# module_tester-v01.net
KiCad netlist of a schematic drawn in EAGLE
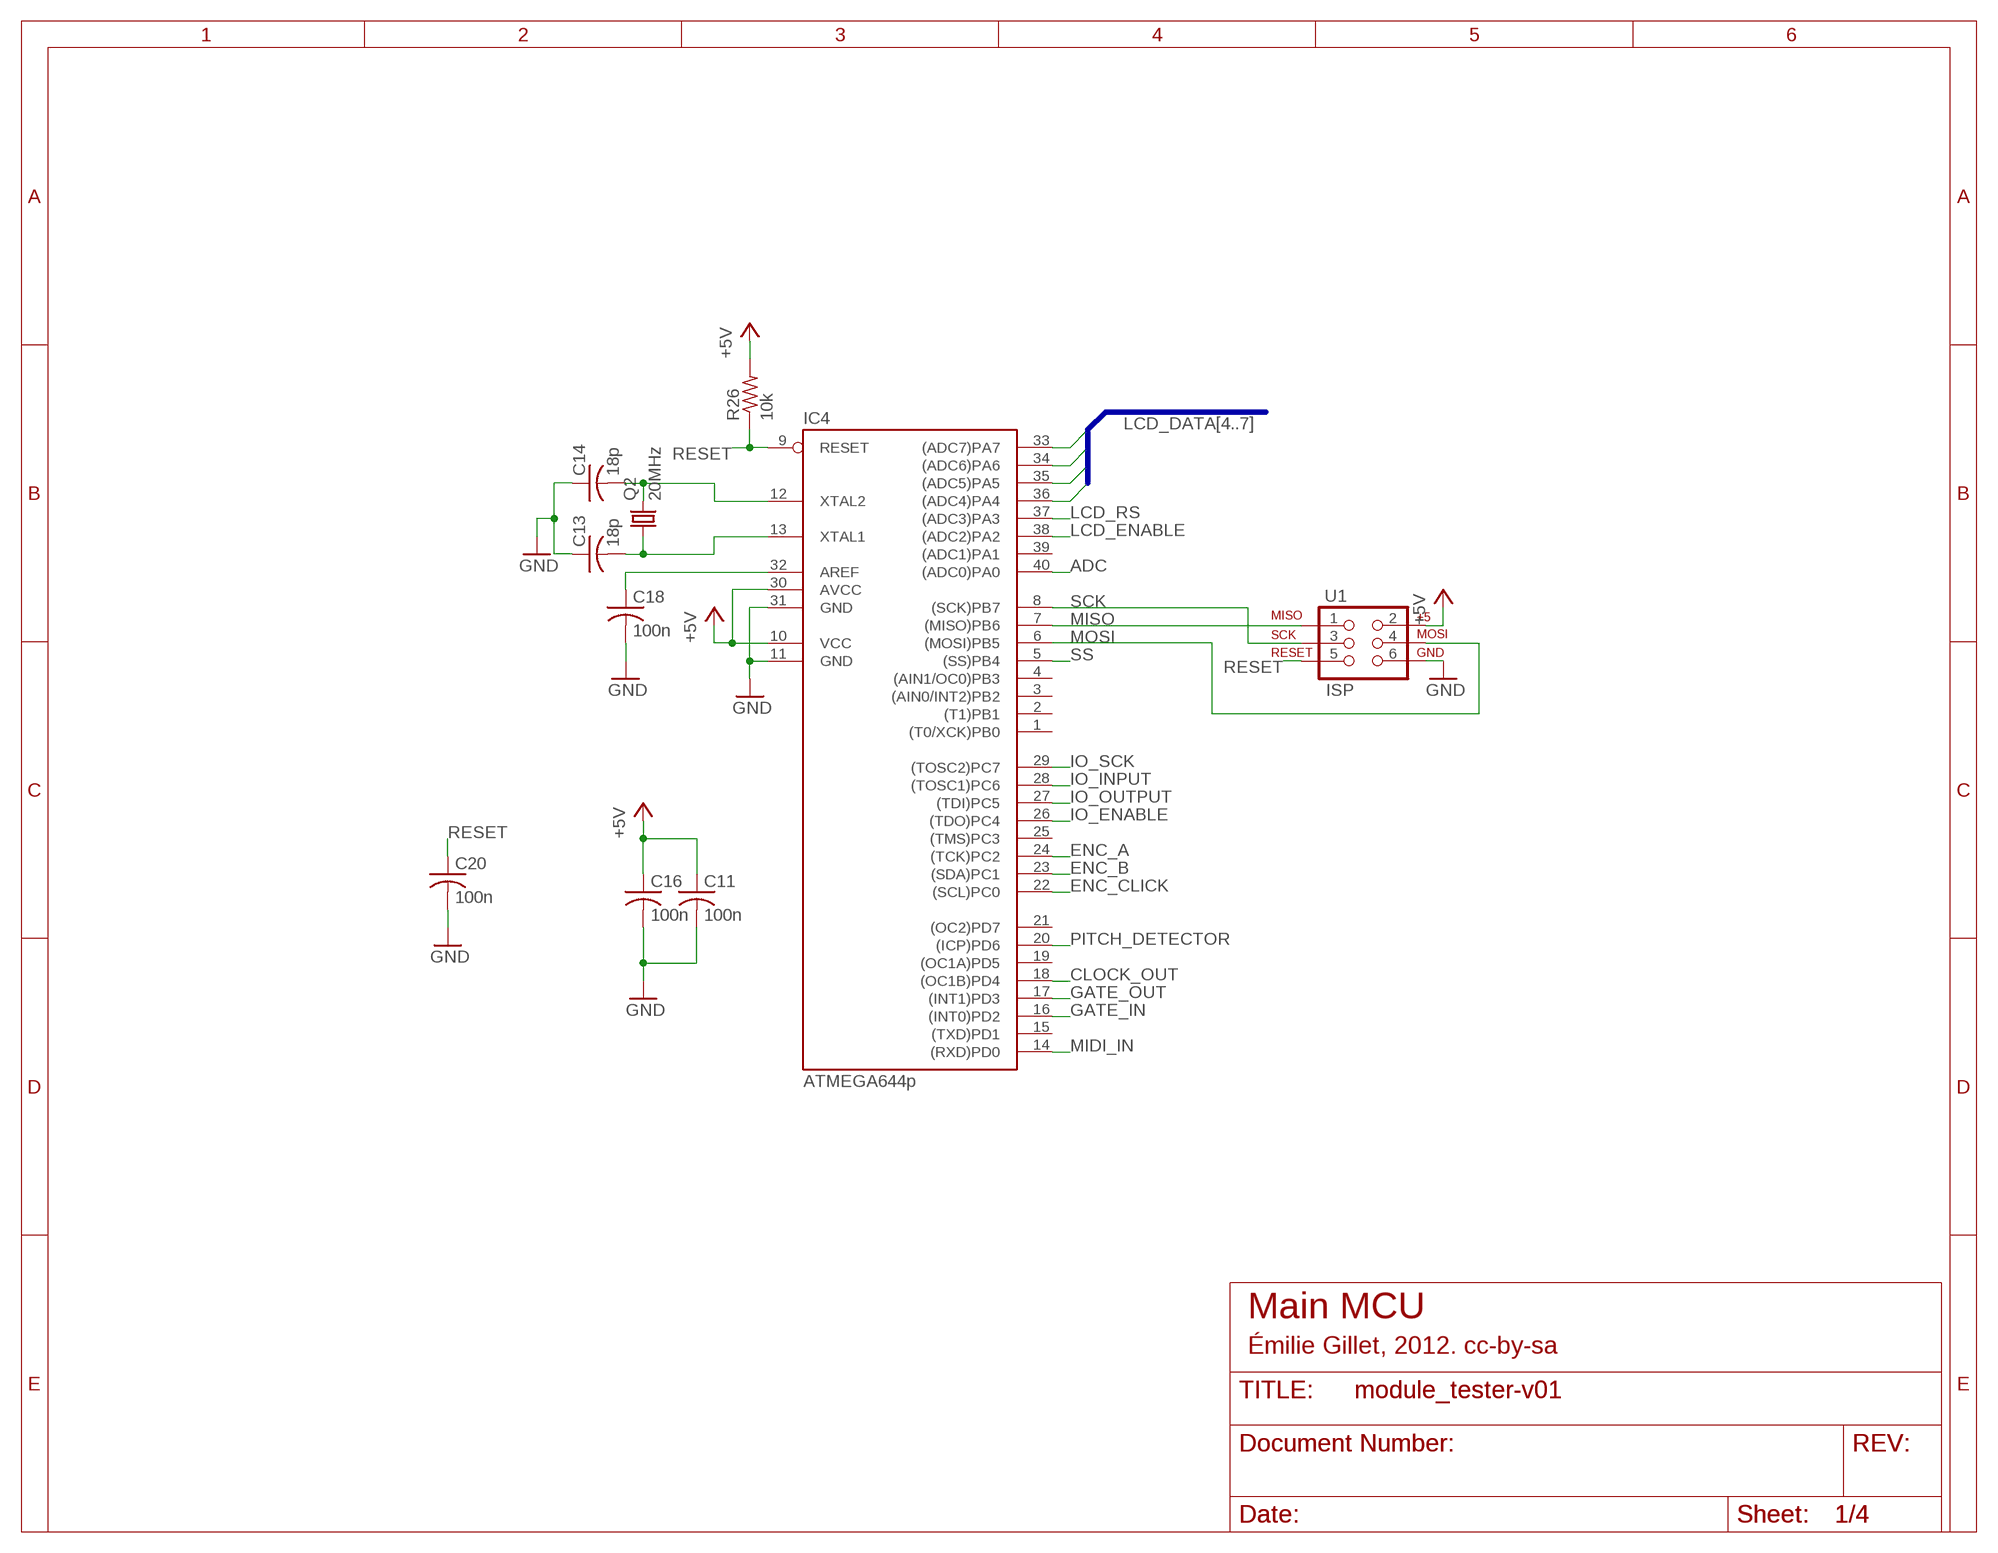
[diagram p0: schematic, sheet 1]
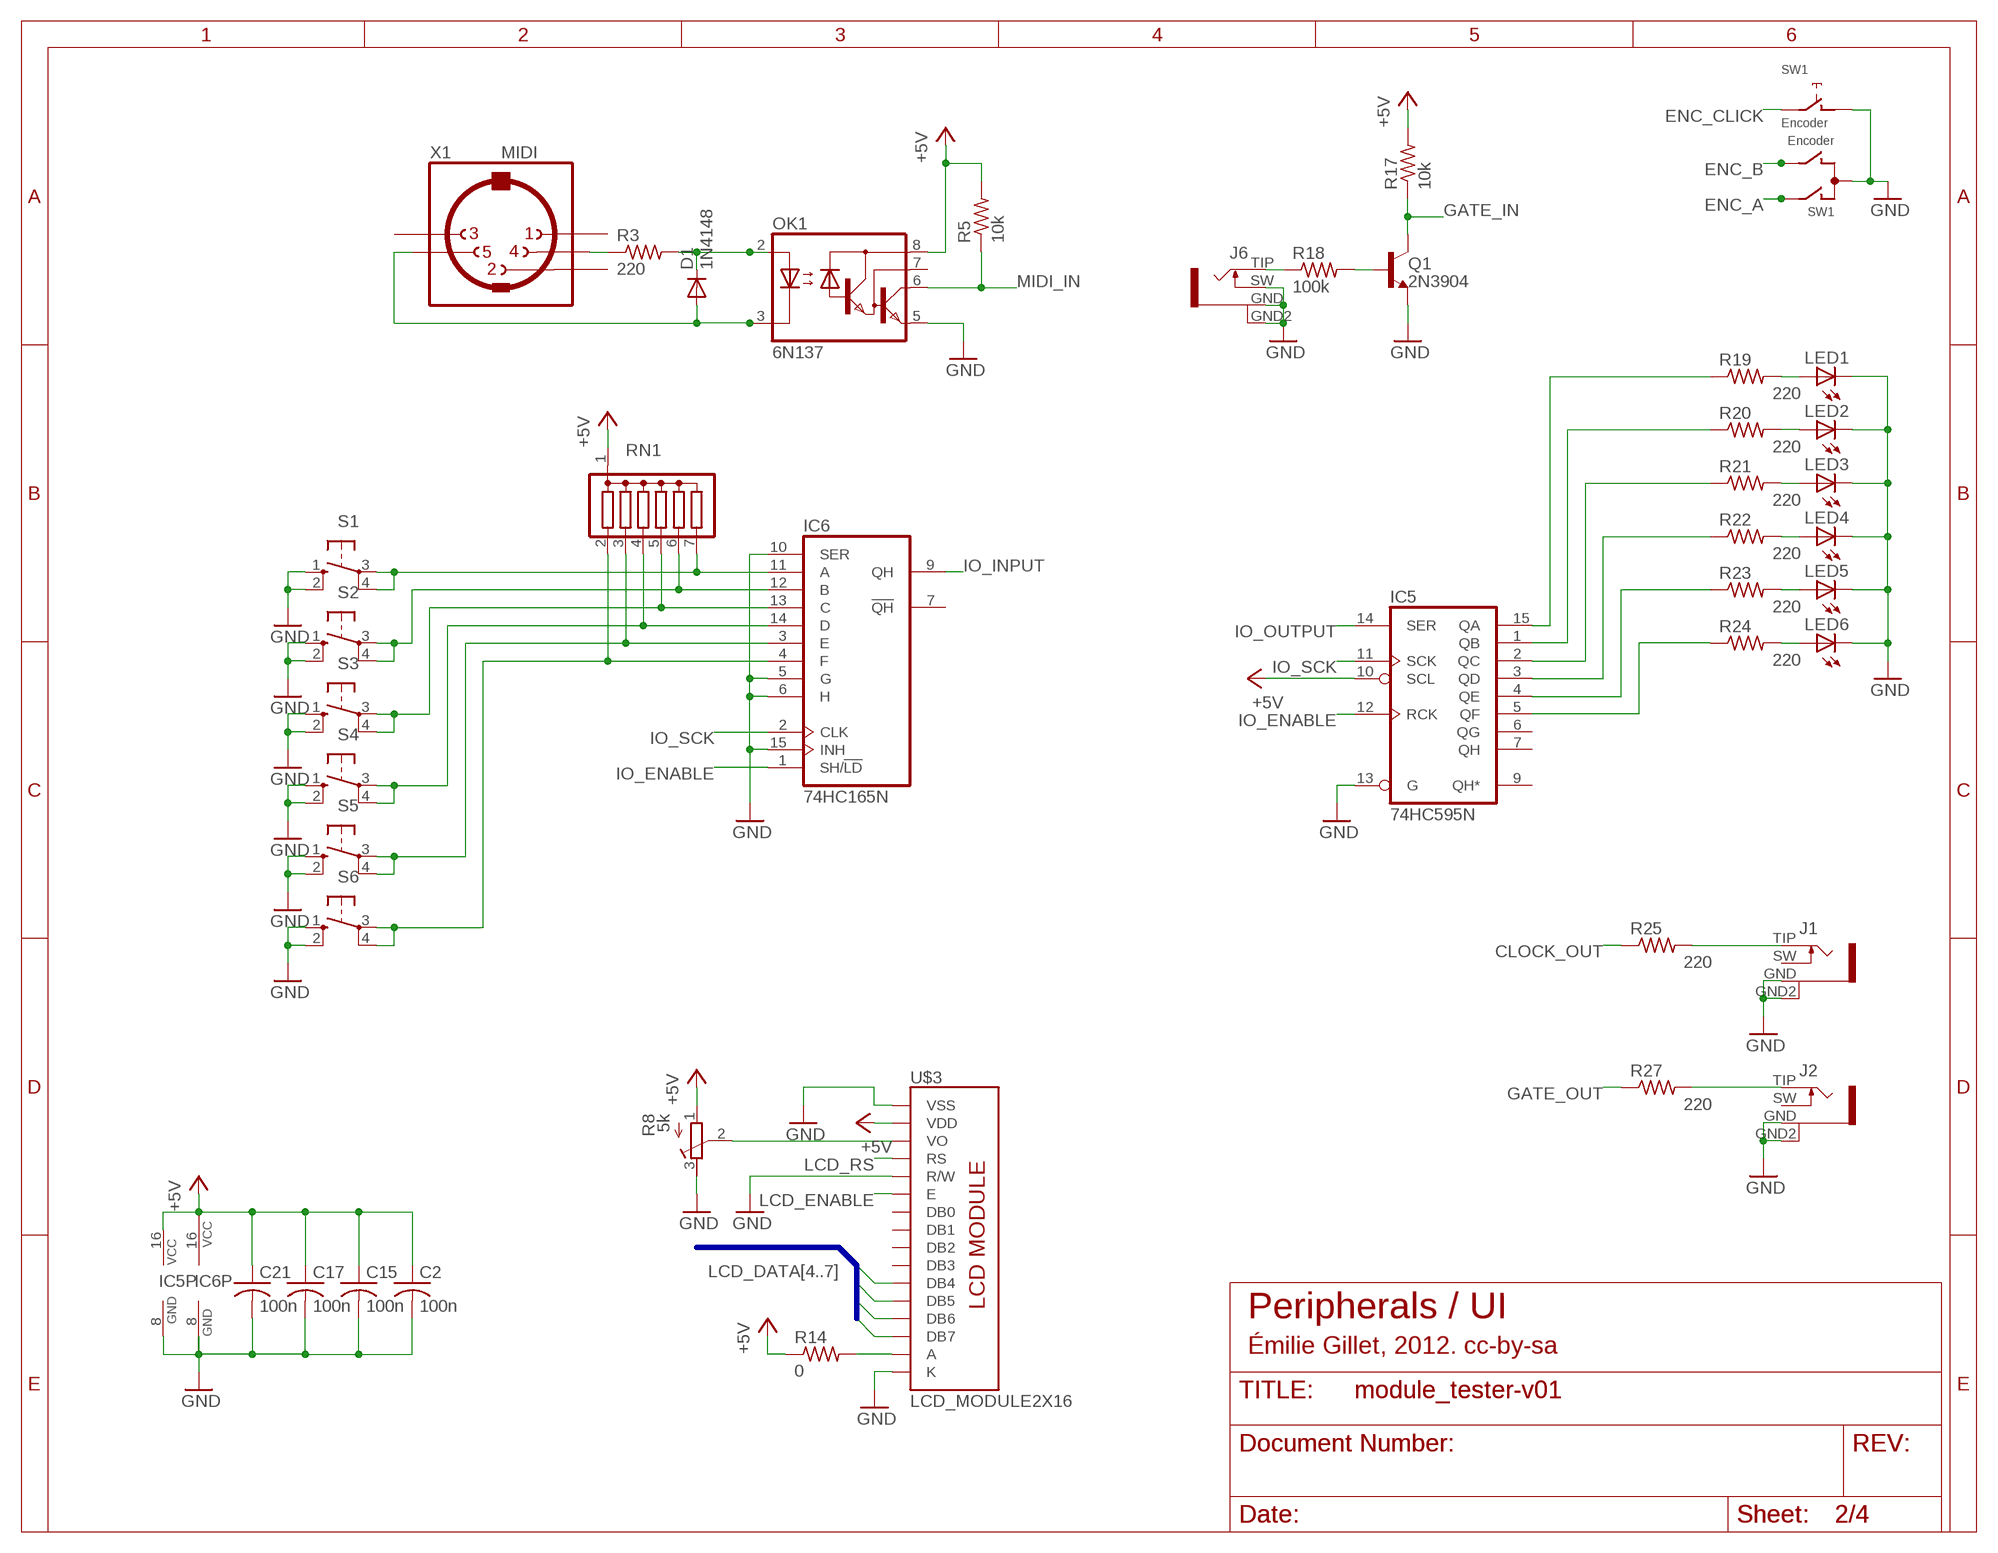
[diagram p1: schematic, sheet 2]
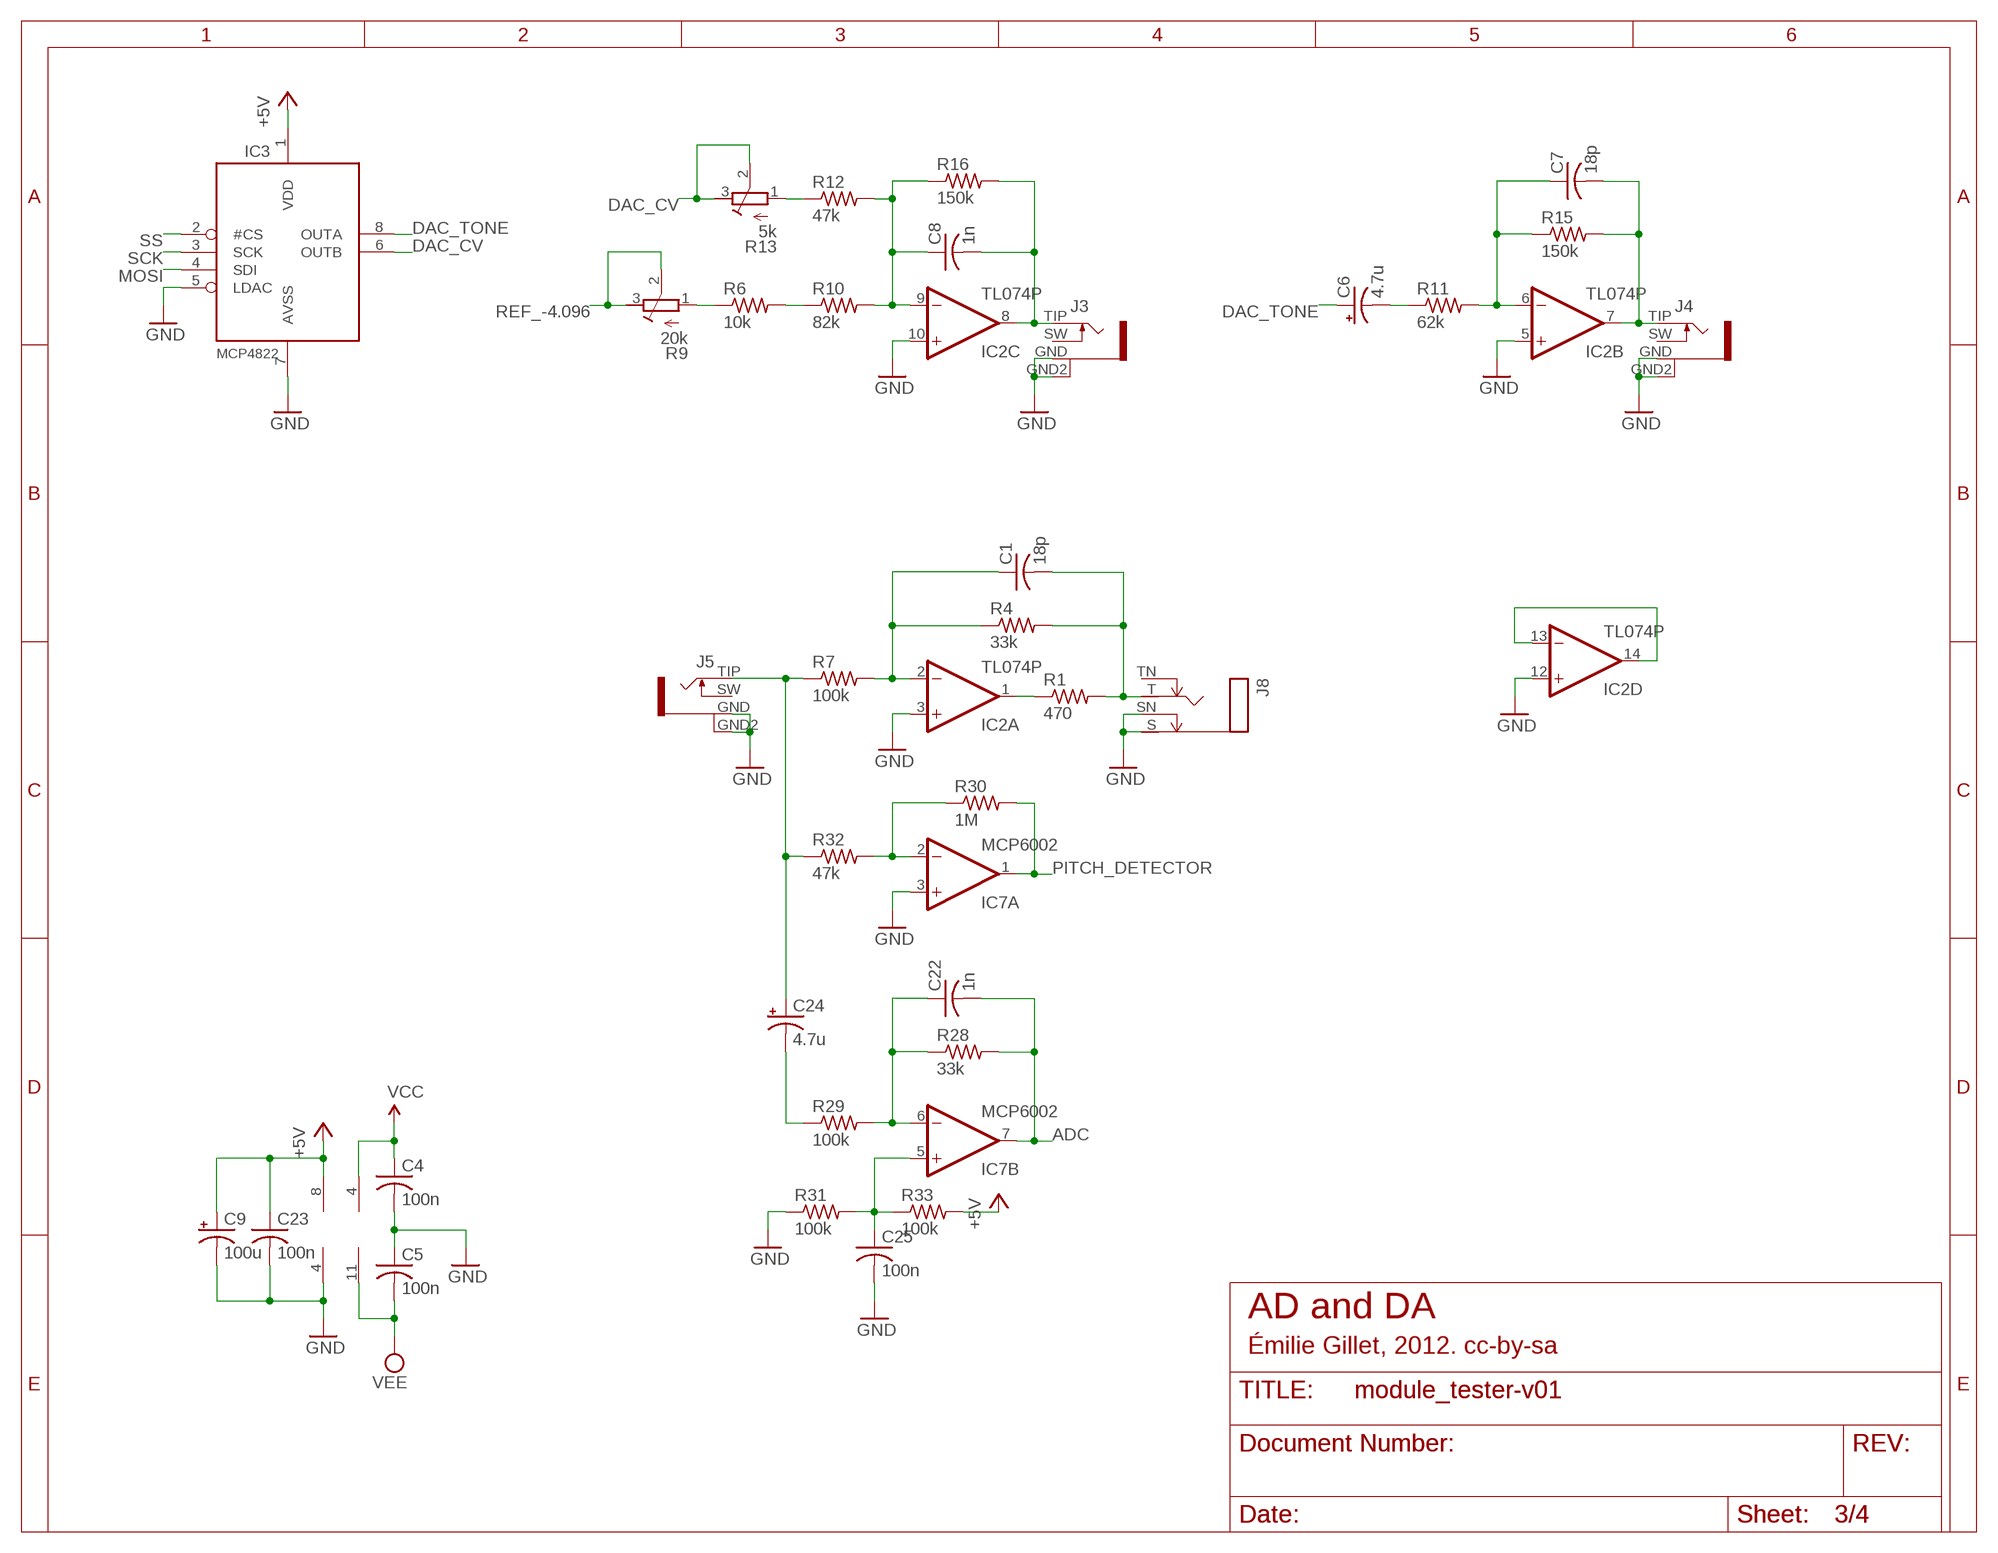
[diagram p2: schematic, sheet 3]
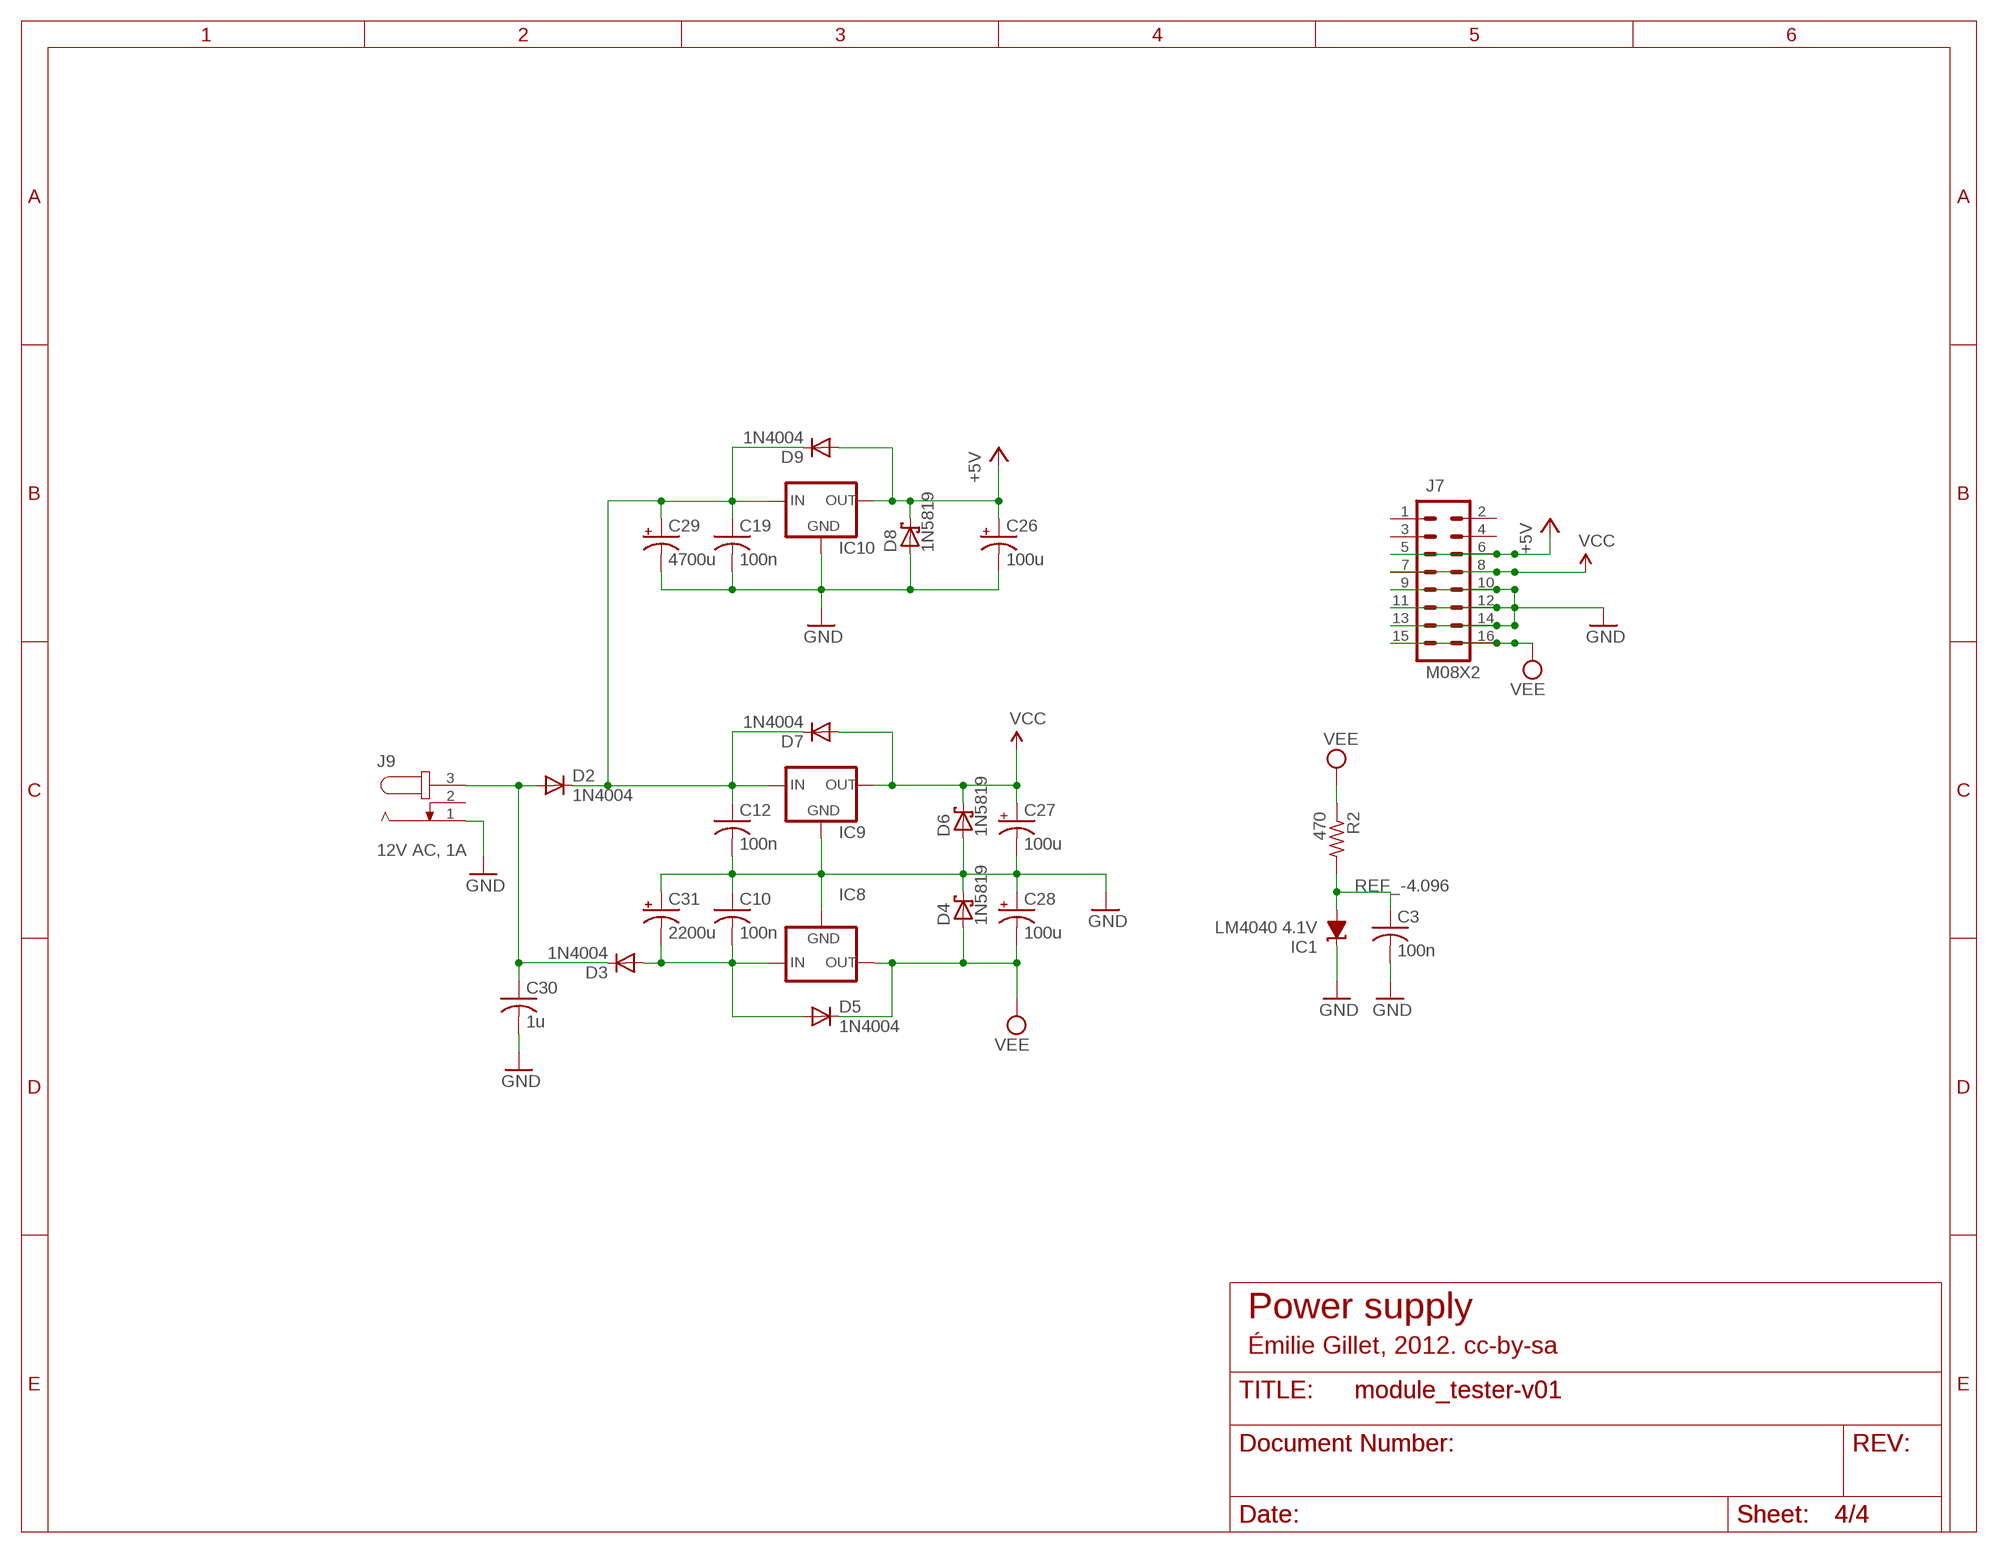
[diagram p3: schematic, sheet 4]

(export (version "E")
  (design (tool "Eeschema 10.0.6"))
  (components
    (comp (ref "C2")
      (value "100n")
      (footprint "eagle-import:C025-025X050")
      (libsource (lib "eagle-import") (part "C-US025-025X050"))
    )
    (comp (ref "C15")
      (value "100n")
      (footprint "eagle-import:C025-025X050")
      (libsource (lib "eagle-import") (part "C-US025-025X050"))
    )
    (comp (ref "C17")
      (value "100n")
      (footprint "eagle-import:C025-025X050")
      (libsource (lib "eagle-import") (part "C-US025-025X050"))
    )
    (comp (ref "C21")
      (value "100n")
      (footprint "eagle-import:C025-025X050")
      (libsource (lib "eagle-import") (part "C-US025-025X050"))
    )
    (comp (ref "D1")
      (value "1N4148")
      (footprint "eagle-import:D-5")
      (libsource (lib "eagle-import") (part "DIODE-D-5"))
    )
    (comp (ref "IC5")
      (value "74HC595N")
      (footprint "eagle-import:DIL16")
      (libsource (lib "eagle-import") (part "74595NHC"))
    )
    (comp (ref "IC6")
      (value "74HC165N")
      (footprint "eagle-import:DIL16")
      (libsource (lib "eagle-import") (part "74165NLS"))
    )
    (comp (ref "J1")
      (value "PJ301WQP")
      (footprint "eagle-import:WQP_PJ_301BM")
      (libsource (lib "eagle-import") (part "PJ301WQP"))
    )
    (comp (ref "J2")
      (value "PJ301WQP")
      (footprint "eagle-import:WQP_PJ_301BM")
      (libsource (lib "eagle-import") (part "PJ301WQP"))
    )
    (comp (ref "J6")
      (value "PJ301WQP")
      (footprint "eagle-import:WQP_PJ_301BM")
      (libsource (lib "eagle-import") (part "PJ301WQP"))
    )
    (comp (ref "LED1")
      (value "LED3MM")
      (footprint "eagle-import:LED3MM")
      (libsource (lib "eagle-import") (part "LED3MM"))
    )
    (comp (ref "LED2")
      (value "LED3MM")
      (footprint "eagle-import:LED3MM")
      (libsource (lib "eagle-import") (part "LED3MM"))
    )
    (comp (ref "LED3")
      (value "LED3MM")
      (footprint "eagle-import:LED3MM")
      (libsource (lib "eagle-import") (part "LED3MM"))
    )
    (comp (ref "LED4")
      (value "LED3MM")
      (footprint "eagle-import:LED3MM")
      (libsource (lib "eagle-import") (part "LED3MM"))
    )
    (comp (ref "LED5")
      (value "LED3MM")
      (footprint "eagle-import:LED3MM")
      (libsource (lib "eagle-import") (part "LED3MM"))
    )
    (comp (ref "LED6")
      (value "LED3MM")
      (footprint "eagle-import:LED3MM")
      (libsource (lib "eagle-import") (part "LED3MM"))
    )
    (comp (ref "OK1")
      (value "6N137")
      (footprint "eagle-import:DIL08")
      (libsource (lib "eagle-import") (part "6N138"))
    )
    (comp (ref "Q1")
      (value "2N3904")
      (footprint "eagle-import:TO92-")
      (libsource (lib "eagle-import") (part "2N3904"))
    )
    (comp (ref "R3")
      (value "220")
      (footprint "eagle-import:0204_7")
      (libsource (lib "eagle-import") (part "R-US_0204/7"))
    )
    (comp (ref "R5")
      (value "10k")
      (footprint "eagle-import:0204_7")
      (libsource (lib "eagle-import") (part "R-US_0204/7"))
    )
    (comp (ref "R8")
      (value "5k")
      (footprint "eagle-import:RTRIM3339P")
      (libsource (lib "eagle-import") (part "R-TRIMM3339P"))
    )
    (comp (ref "R14")
      (value "0")
      (footprint "eagle-import:0204_7")
      (libsource (lib "eagle-import") (part "R-US_0204/7"))
    )
    (comp (ref "R17")
      (value "10k")
      (footprint "eagle-import:0204_7")
      (libsource (lib "eagle-import") (part "R-US_0204/7"))
    )
    (comp (ref "R18")
      (value "100k")
      (footprint "eagle-import:0204_7")
      (libsource (lib "eagle-import") (part "R-US_0204/7"))
    )
    (comp (ref "R19")
      (value "220")
      (footprint "eagle-import:0204_7")
      (libsource (lib "eagle-import") (part "R-US_0204/7"))
    )
    (comp (ref "R20")
      (value "220")
      (footprint "eagle-import:0204_7")
      (libsource (lib "eagle-import") (part "R-US_0204/7"))
    )
    (comp (ref "R21")
      (value "220")
      (footprint "eagle-import:0204_7")
      (libsource (lib "eagle-import") (part "R-US_0204/7"))
    )
    (comp (ref "R22")
      (value "220")
      (footprint "eagle-import:0204_7")
      (libsource (lib "eagle-import") (part "R-US_0204/7"))
    )
    (comp (ref "R23")
      (value "220")
      (footprint "eagle-import:0204_7")
      (libsource (lib "eagle-import") (part "R-US_0204/7"))
    )
    (comp (ref "R24")
      (value "220")
      (footprint "eagle-import:0204_7")
      (libsource (lib "eagle-import") (part "R-US_0204/7"))
    )
    (comp (ref "R25")
      (value "220")
      (footprint "eagle-import:0204_7")
      (libsource (lib "eagle-import") (part "R-US_0204/7"))
    )
    (comp (ref "R27")
      (value "220")
      (footprint "eagle-import:0204_7")
      (libsource (lib "eagle-import") (part "R-US_0204/7"))
    )
    (comp (ref "RN1")
      (value "G06R")
      (footprint "eagle-import:SIL7")
      (libsource (lib "eagle-import") (part "G06R"))
    )
    (comp (ref "S1")
      (value "40-XX")
      (footprint "eagle-import:B3F-40XX")
      (libsource (lib "eagle-import") (part "40-XX"))
    )
    (comp (ref "S2")
      (value "40-XX")
      (footprint "eagle-import:B3F-40XX")
      (libsource (lib "eagle-import") (part "40-XX"))
    )
    (comp (ref "S3")
      (value "40-XX")
      (footprint "eagle-import:B3F-40XX")
      (libsource (lib "eagle-import") (part "40-XX"))
    )
    (comp (ref "S4")
      (value "40-XX")
      (footprint "eagle-import:B3F-40XX")
      (libsource (lib "eagle-import") (part "40-XX"))
    )
    (comp (ref "S5")
      (value "40-XX")
      (footprint "eagle-import:B3F-40XX")
      (libsource (lib "eagle-import") (part "40-XX"))
    )
    (comp (ref "S6")
      (value "40-XX")
      (footprint "eagle-import:B3F-40XX")
      (libsource (lib "eagle-import") (part "40-XX"))
    )
    (comp (ref "SW1")
      (value "Encoder")
      (footprint "eagle-import:ALPS_EC12E_SW")
      (libsource (lib "eagle-import") (part "EC12E_SW"))
    )
    (comp (ref "U$3")
      (value "LCD_MODULE2X16")
      (footprint "eagle-import:LCD_MODULE_2X16")
      (libsource (lib "eagle-import") (part "LCD_MODULE2X16"))
    )
    (comp (ref "X1")
      (value "MIDI")
      (footprint "eagle-import:MAB5SH")
      (libsource (lib "eagle-import") (part "MAB5SH"))
    )
    (comp (ref "C1")
      (value "18p")
      (footprint "eagle-import:C025-025X050")
      (libsource (lib "eagle-import") (part "C-US025-025X050"))
    )
    (comp (ref "C4")
      (value "100n")
      (footprint "eagle-import:C025-025X050")
      (libsource (lib "eagle-import") (part "C-US025-025X050"))
    )
    (comp (ref "C5")
      (value "100n")
      (footprint "eagle-import:C025-025X050")
      (libsource (lib "eagle-import") (part "C-US025-025X050"))
    )
    (comp (ref "C6")
      (value "4.7u")
      (footprint "eagle-import:E2,5-6")
      (libsource (lib "eagle-import") (part "CPOL-USE2.5-6"))
    )
    (comp (ref "C7")
      (value "18p")
      (footprint "eagle-import:C025-025X050")
      (libsource (lib "eagle-import") (part "C-US025-025X050"))
    )
    (comp (ref "C8")
      (value "1n")
      (footprint "eagle-import:C025-025X050")
      (libsource (lib "eagle-import") (part "C-US025-025X050"))
    )
    (comp (ref "C9")
      (value "100u")
      (footprint "eagle-import:E2,5-7")
      (libsource (lib "eagle-import") (part "CPOL-USE2.5-7"))
    )
    (comp (ref "C22")
      (value "1n")
      (footprint "eagle-import:C025-025X050")
      (libsource (lib "eagle-import") (part "C-US025-025X050"))
    )
    (comp (ref "C23")
      (value "100n")
      (footprint "eagle-import:C025-025X050")
      (libsource (lib "eagle-import") (part "C-US025-025X050"))
    )
    (comp (ref "C24")
      (value "4.7u")
      (footprint "eagle-import:E2,5-6")
      (libsource (lib "eagle-import") (part "CPOL-USE2.5-6"))
    )
    (comp (ref "C25")
      (value "100n")
      (footprint "eagle-import:C025-025X050")
      (libsource (lib "eagle-import") (part "C-US025-025X050"))
    )
    (comp (ref "IC2")
      (value "TL074P")
      (footprint "eagle-import:DIL14")
      (libsource (lib "eagle-import") (part "TL074P"))
    )
    (comp (ref "IC3")
      (value "MCP4822")
      (footprint "eagle-import:DIL08")
      (libsource (lib "eagle-import") (part "MCP4822"))
    )
    (comp (ref "IC7")
      (value "MCP6002")
      (footprint "eagle-import:DIL08")
      (libsource (lib "eagle-import") (part "TL072P"))
    )
    (comp (ref "J3")
      (value "PJ301WQP")
      (footprint "eagle-import:WQP_PJ_301BM")
      (libsource (lib "eagle-import") (part "PJ301WQP"))
    )
    (comp (ref "J4")
      (value "PJ301WQP")
      (footprint "eagle-import:WQP_PJ_301BM")
      (libsource (lib "eagle-import") (part "PJ301WQP"))
    )
    (comp (ref "J5")
      (value "PJ301WQP")
      (footprint "eagle-import:WQP_PJ_301BM")
      (libsource (lib "eagle-import") (part "PJ301WQP"))
    )
    (comp (ref "J8")
      (value "MONOSWSLIM")
      (footprint "eagle-import:NRJ4HF")
      (libsource (lib "eagle-import") (part "MONOSWSLIM"))
    )
    (comp (ref "R1")
      (value "470")
      (footprint "eagle-import:0204_7")
      (libsource (lib "eagle-import") (part "R-US_0204/7"))
    )
    (comp (ref "R4")
      (value "33k")
      (footprint "eagle-import:0204_7")
      (libsource (lib "eagle-import") (part "R-US_0204/7"))
    )
    (comp (ref "R6")
      (value "10k")
      (footprint "eagle-import:0204_7")
      (libsource (lib "eagle-import") (part "R-US_0204/7"))
    )
    (comp (ref "R7")
      (value "100k")
      (footprint "eagle-import:0204_7")
      (libsource (lib "eagle-import") (part "R-US_0204/7"))
    )
    (comp (ref "R9")
      (value "20k")
      (footprint "eagle-import:RTRIM3296W")
      (libsource (lib "eagle-import") (part "R-TRIMM3296W"))
    )
    (comp (ref "R10")
      (value "82k")
      (footprint "eagle-import:0204_7")
      (libsource (lib "eagle-import") (part "R-US_0204/7"))
    )
    (comp (ref "R11")
      (value "62k")
      (footprint "eagle-import:0204_7")
      (libsource (lib "eagle-import") (part "R-US_0204/7"))
    )
    (comp (ref "R12")
      (value "47k")
      (footprint "eagle-import:0204_7")
      (libsource (lib "eagle-import") (part "R-US_0204/7"))
    )
    (comp (ref "R13")
      (value "5k")
      (footprint "eagle-import:RTRIM3296W")
      (libsource (lib "eagle-import") (part "R-TRIMM3296W"))
    )
    (comp (ref "R15")
      (value "150k")
      (footprint "eagle-import:0204_7")
      (libsource (lib "eagle-import") (part "R-US_0204/7"))
    )
    (comp (ref "R16")
      (value "150k")
      (footprint "eagle-import:0204_7")
      (libsource (lib "eagle-import") (part "R-US_0204/7"))
    )
    (comp (ref "R28")
      (value "33k")
      (footprint "eagle-import:0204_7")
      (libsource (lib "eagle-import") (part "R-US_0204/7"))
    )
    (comp (ref "R29")
      (value "100k")
      (footprint "eagle-import:0204_7")
      (libsource (lib "eagle-import") (part "R-US_0204/7"))
    )
    (comp (ref "R30")
      (value "1M")
      (footprint "eagle-import:0204_7")
      (libsource (lib "eagle-import") (part "R-US_0204/7"))
    )
    (comp (ref "R31")
      (value "100k")
      (footprint "eagle-import:0204_7")
      (libsource (lib "eagle-import") (part "R-US_0204/7"))
    )
    (comp (ref "R32")
      (value "47k")
      (footprint "eagle-import:0204_7")
      (libsource (lib "eagle-import") (part "R-US_0204/7"))
    )
    (comp (ref "R33")
      (value "100k")
      (footprint "eagle-import:0204_7")
      (libsource (lib "eagle-import") (part "R-US_0204/7"))
    )
    (comp (ref "C11")
      (value "100n")
      (footprint "eagle-import:C025-025X050")
      (libsource (lib "eagle-import") (part "C-US025-025X050"))
    )
    (comp (ref "C13")
      (value "18p")
      (footprint "eagle-import:C025-025X050")
      (libsource (lib "eagle-import") (part "C-US025-025X050"))
    )
    (comp (ref "C14")
      (value "18p")
      (footprint "eagle-import:C025-025X050")
      (libsource (lib "eagle-import") (part "C-US025-025X050"))
    )
    (comp (ref "C16")
      (value "100n")
      (footprint "eagle-import:C025-025X050")
      (libsource (lib "eagle-import") (part "C-US025-025X050"))
    )
    (comp (ref "C18")
      (value "100n")
      (footprint "eagle-import:C025-025X050")
      (libsource (lib "eagle-import") (part "C-US025-025X050"))
    )
    (comp (ref "C20")
      (value "100n")
      (footprint "eagle-import:C025-025X050")
      (libsource (lib "eagle-import") (part "C-US025-025X050"))
    )
    (comp (ref "IC4")
      (value "ATMEGA644p")
      (footprint "eagle-import:DIL40")
      (libsource (lib "eagle-import") (part "MEGA16-P"))
    )
    (comp (ref "Q2")
      (value "20MHz")
      (footprint "eagle-import:HC49U-V")
      (libsource (lib "eagle-import") (part "CRYSTALHC49U-V"))
    )
    (comp (ref "R26")
      (value "10k")
      (footprint "eagle-import:0204_7")
      (libsource (lib "eagle-import") (part "R-US_0204/7"))
    )
    (comp (ref "U1")
      (value "ISP")
      (footprint "eagle-import:2X3")
      (libsource (lib "eagle-import") (part "AVR_SPI_PRG_6PTH"))
    )
    (comp (ref "C3")
      (value "100n")
      (footprint "eagle-import:C025-025X050")
      (libsource (lib "eagle-import") (part "C-US025-025X050"))
    )
    (comp (ref "C10")
      (value "100n")
      (footprint "eagle-import:C025-025X050")
      (libsource (lib "eagle-import") (part "C-US025-025X050"))
    )
    (comp (ref "C12")
      (value "100n")
      (footprint "eagle-import:C025-025X050")
      (libsource (lib "eagle-import") (part "C-US025-025X050"))
    )
    (comp (ref "C19")
      (value "100n")
      (footprint "eagle-import:C025-025X050")
      (libsource (lib "eagle-import") (part "C-US025-025X050"))
    )
    (comp (ref "C26")
      (value "100u")
      (footprint "eagle-import:E2,5-7")
      (libsource (lib "eagle-import") (part "CPOL-USE2.5-7"))
    )
    (comp (ref "C27")
      (value "100u")
      (footprint "eagle-import:E2,5-7")
      (libsource (lib "eagle-import") (part "CPOL-USE2.5-7"))
    )
    (comp (ref "C28")
      (value "100u")
      (footprint "eagle-import:E2,5-7")
      (libsource (lib "eagle-import") (part "CPOL-USE2.5-7"))
    )
    (comp (ref "C29")
      (value "4700u")
      (footprint "eagle-import:E7,5-16")
      (libsource (lib "eagle-import") (part "CPOL-USE7.5-16"))
    )
    (comp (ref "C30")
      (value "1u")
      (footprint "eagle-import:C075-052X106")
      (libsource (lib "eagle-import") (part "C-US075-052X106"))
    )
    (comp (ref "C31")
      (value "2200u")
      (footprint "eagle-import:E5-13")
      (libsource (lib "eagle-import") (part "CPOL-USE5-13"))
    )
    (comp (ref "D2")
      (value "1N4004")
      (footprint "eagle-import:DO41-10")
      (libsource (lib "eagle-import") (part "1N4004"))
    )
    (comp (ref "D3")
      (value "1N4004")
      (footprint "eagle-import:DO41-10")
      (libsource (lib "eagle-import") (part "1N4004"))
    )
    (comp (ref "D4")
      (value "1N5819")
      (footprint "eagle-import:DO41-7.6")
      (libsource (lib "eagle-import") (part "1N5819-T"))
    )
    (comp (ref "D5")
      (value "1N4004")
      (footprint "eagle-import:DO41-10")
      (libsource (lib "eagle-import") (part "1N4004"))
    )
    (comp (ref "D6")
      (value "1N5819")
      (footprint "eagle-import:DO41-7.6")
      (libsource (lib "eagle-import") (part "1N5819-T"))
    )
    (comp (ref "D7")
      (value "1N4004")
      (footprint "eagle-import:DO41-10")
      (libsource (lib "eagle-import") (part "1N4004"))
    )
    (comp (ref "D8")
      (value "1N5819")
      (footprint "eagle-import:DO41-7.6")
      (libsource (lib "eagle-import") (part "1N5819-T"))
    )
    (comp (ref "D9")
      (value "1N4004")
      (footprint "eagle-import:DO41-10")
      (libsource (lib "eagle-import") (part "1N4004"))
    )
    (comp (ref "IC1")
      (value "LM4040 4.1V")
      (footprint "eagle-import:LP_O-PBCY-W3")
      (libsource (lib "eagle-import") (part "LM4041LPC12"))
    )
    (comp (ref "IC8")
      (value "79XXL")
      (footprint "eagle-import:79XXL")
      (libsource (lib "eagle-import") (part "79XXL"))
    )
    (comp (ref "IC9")
      (value "78XXL")
      (footprint "eagle-import:78XXL")
      (libsource (lib "eagle-import") (part "78XXL"))
    )
    (comp (ref "IC10")
      (value "78XXL")
      (footprint "eagle-import:78XXL")
      (libsource (lib "eagle-import") (part "78XXL"))
    )
    (comp (ref "J7")
      (value "M08X2")
      (footprint "eagle-import:2X8")
      (libsource (lib "eagle-import") (part "M08X2"))
    )
    (comp (ref "J9")
      (value "JACK-PLUG2")
      (footprint "eagle-import:SPC4078_BIG_HOLES")
      (libsource (lib "eagle-import") (part "JACK-PLUG2"))
    )
    (comp (ref "R2")
      (value "470")
      (footprint "eagle-import:0204_7")
      (libsource (lib "eagle-import") (part "resistor_R-US_0204/7"))
    )
  )
  (nets
    (net (code "1") (name "+5V") (class "Default")
      (node (ref "C11") (pin "1") (pinfunction "1_1") (pintype "passive"))
      (node (ref "C15") (pin "1") (pinfunction "1_1") (pintype "passive"))
      (node (ref "C16") (pin "1") (pinfunction "1_1") (pintype "passive"))
      (node (ref "C17") (pin "1") (pinfunction "1_1") (pintype "passive"))
      (node (ref "C2") (pin "1") (pinfunction "1_1") (pintype "passive"))
      (node (ref "C21") (pin "1") (pinfunction "1_1") (pintype "passive"))
      (node (ref "C23") (pin "1") (pinfunction "1_1") (pintype "passive"))
      (node (ref "C26") (pin "+") (pinfunction "+_+") (pintype "passive"))
      (node (ref "C9") (pin "+") (pinfunction "+_+") (pintype "passive"))
      (node (ref "D8") (pin "C") (pinfunction "C_C") (pintype "passive"))
      (node (ref "D9") (pin "A") (pinfunction "A_A") (pintype "passive"))
      (node (ref "IC10") (pin "OUT") (pinfunction "OUT_OUT") (pintype "passive"))
      (node (ref "IC3") (pin "1") (pinfunction "VDD_1") (pintype "power_in"))
      (node (ref "IC4") (pin "10") (pinfunction "VCC_10") (pintype "power_in"))
      (node (ref "IC4") (pin "30") (pinfunction "AVCC_30") (pintype "power_in"))
      (node (ref "IC5") (pin "10") (pinfunction "SCL_10") (pintype "input"))
      (node (ref "IC5") (pin "16") (pinfunction "VCC_16") (pintype "power_in"))
      (node (ref "IC6") (pin "16") (pinfunction "VCC_16") (pintype "power_in"))
      (node (ref "IC7") (pin "8") (pinfunction "V+_8") (pintype "power_in"))
      (node (ref "J7") (pin "5") (pinfunction "5_5") (pintype "passive"))
      (node (ref "J7") (pin "6") (pinfunction "6_6") (pintype "passive"))
      (node (ref "OK1") (pin "8") (pinfunction "VCC_8") (pintype "passive"))
      (node (ref "R14") (pin "1") (pinfunction "1_1") (pintype "passive"))
      (node (ref "R17") (pin "2") (pinfunction "2_2") (pintype "passive"))
      (node (ref "R26") (pin "2") (pinfunction "2_2") (pintype "passive"))
      (node (ref "R33") (pin "2") (pinfunction "2_2") (pintype "passive"))
      (node (ref "R5") (pin "2") (pinfunction "2_2") (pintype "passive"))
      (node (ref "R8") (pin "1") (pinfunction "E_1") (pintype "passive"))
      (node (ref "RN1") (pin "1") (pinfunction "1_1") (pintype "passive"))
      (node (ref "U$3") (pin "2") (pinfunction "VDD_2") (pintype "power_in"))
      (node (ref "U1") (pin "2") (pinfunction "2_2") (pintype "passive"))
    )
    (net (code "4") (name "ADC") (class "Default")
      (node (ref "C22") (pin "2") (pinfunction "2_2") (pintype "passive"))
      (node (ref "IC4") (pin "40") (pinfunction "(ADC0)PA0_40") (pintype "bidirectional"))
      (node (ref "IC7") (pin "7") (pinfunction "OUT_7") (pintype "output"))
      (node (ref "R28") (pin "2") (pinfunction "2_2") (pintype "passive"))
    )
    (net (code "5") (name "CLOCK_OUT") (class "Default")
      (node (ref "IC4") (pin "18") (pinfunction "(OC1B)PD4_18") (pintype "bidirectional"))
      (node (ref "R25") (pin "1") (pinfunction "1_1") (pintype "passive"))
    )
    (net (code "6") (name "DAC_CV") (class "Default")
      (node (ref "IC3") (pin "6") (pinfunction "OUTB_6") (pintype "output"))
      (node (ref "R13") (pin "2") (pinfunction "S_2") (pintype "passive"))
      (node (ref "R13") (pin "3") (pinfunction "A_3") (pintype "passive"))
    )
    (net (code "7") (name "DAC_TONE") (class "Default")
      (node (ref "C6") (pin "+") (pinfunction "+_+") (pintype "passive"))
      (node (ref "IC3") (pin "8") (pinfunction "OUTA_8") (pintype "output"))
    )
    (net (code "8") (name "ENC_A") (class "Default")
      (node (ref "IC4") (pin "24") (pinfunction "(TCK)PC2_24") (pintype "bidirectional"))
      (node (ref "SW1") (pin "A") (pinfunction "A_A") (pintype "passive"))
    )
    (net (code "9") (name "ENC_B") (class "Default")
      (node (ref "IC4") (pin "23") (pinfunction "(SDA)PC1_23") (pintype "bidirectional"))
      (node (ref "SW1") (pin "B") (pinfunction "B_B") (pintype "passive"))
    )
    (net (code "10") (name "ENC_CLICK") (class "Default")
      (node (ref "IC4") (pin "22") (pinfunction "(SCL)PC0_22") (pintype "bidirectional"))
      (node (ref "SW1") (pin "E") (pinfunction "2_E") (pintype "passive"))
    )
    (net (code "11") (name "GATE_IN") (class "Default")
      (node (ref "IC4") (pin "16") (pinfunction "(INT0)PD2_16") (pintype "bidirectional"))
      (node (ref "Q1") (pin "1") (pinfunction "C_1") (pintype "passive"))
      (node (ref "R17") (pin "1") (pinfunction "1_1") (pintype "passive"))
    )
    (net (code "12") (name "GATE_OUT") (class "Default")
      (node (ref "IC4") (pin "17") (pinfunction "(INT1)PD3_17") (pintype "bidirectional"))
      (node (ref "R27") (pin "1") (pinfunction "1_1") (pintype "passive"))
    )
    (net (code "13") (name "GND") (class "Default")
      (node (ref "C10") (pin "1") (pinfunction "1_1") (pintype "passive"))
      (node (ref "C11") (pin "2") (pinfunction "2_2") (pintype "passive"))
      (node (ref "C12") (pin "2") (pinfunction "2_2") (pintype "passive"))
      (node (ref "C13") (pin "1") (pinfunction "1_1") (pintype "passive"))
      (node (ref "C14") (pin "1") (pinfunction "1_1") (pintype "passive"))
      (node (ref "C15") (pin "2") (pinfunction "2_2") (pintype "passive"))
      (node (ref "C16") (pin "2") (pinfunction "2_2") (pintype "passive"))
      (node (ref "C17") (pin "2") (pinfunction "2_2") (pintype "passive"))
      (node (ref "C18") (pin "2") (pinfunction "2_2") (pintype "passive"))
      (node (ref "C19") (pin "2") (pinfunction "2_2") (pintype "passive"))
      (node (ref "C2") (pin "2") (pinfunction "2_2") (pintype "passive"))
      (node (ref "C20") (pin "2") (pinfunction "2_2") (pintype "passive"))
      (node (ref "C21") (pin "2") (pinfunction "2_2") (pintype "passive"))
      (node (ref "C23") (pin "2") (pinfunction "2_2") (pintype "passive"))
      (node (ref "C25") (pin "2") (pinfunction "2_2") (pintype "passive"))
      (node (ref "C26") (pin "-") (pinfunction "-_-") (pintype "passive"))
      (node (ref "C27") (pin "-") (pinfunction "-_-") (pintype "passive"))
      (node (ref "C28") (pin "+") (pinfunction "+_+") (pintype "passive"))
      (node (ref "C29") (pin "-") (pinfunction "-_-") (pintype "passive"))
      (node (ref "C3") (pin "2") (pinfunction "2_2") (pintype "passive"))
      (node (ref "C30") (pin "2") (pinfunction "2_2") (pintype "passive"))
      (node (ref "C31") (pin "+") (pinfunction "+_+") (pintype "passive"))
      (node (ref "C4") (pin "2") (pinfunction "2_2") (pintype "passive"))
      (node (ref "C5") (pin "1") (pinfunction "1_1") (pintype "passive"))
      (node (ref "C9") (pin "-") (pinfunction "-_-") (pintype "passive"))
      (node (ref "D4") (pin "C") (pinfunction "C_C") (pintype "passive"))
      (node (ref "D6") (pin "A") (pinfunction "A_A") (pintype "passive"))
      (node (ref "D8") (pin "A") (pinfunction "A_A") (pintype "passive"))
      (node (ref "IC1") (pin "2") (pinfunction "C_2") (pintype "passive"))
      (node (ref "IC10") (pin "GND") (pinfunction "GND_GND") (pintype "input"))
      (node (ref "IC2") (pin "10") (pinfunction "+IN_10") (pintype "input"))
      (node (ref "IC2") (pin "12") (pinfunction "+IN_12") (pintype "input"))
      (node (ref "IC2") (pin "3") (pinfunction "+IN_3") (pintype "input"))
      (node (ref "IC2") (pin "5") (pinfunction "+IN_5") (pintype "input"))
      (node (ref "IC3") (pin "5") (pinfunction "LDAC_5") (pintype "input"))
      (node (ref "IC3") (pin "7") (pinfunction "AVSS_7") (pintype "power_in"))
      (node (ref "IC4") (pin "11") (pinfunction "GND_11") (pintype "power_in"))
      (node (ref "IC4") (pin "31") (pinfunction "GND_31") (pintype "power_in"))
      (node (ref "IC5") (pin "13") (pinfunction "G_13") (pintype "input"))
      (node (ref "IC5") (pin "8") (pinfunction "GND_8") (pintype "power_in"))
      (node (ref "IC6") (pin "10") (pinfunction "SER_10") (pintype "input"))
      (node (ref "IC6") (pin "15") (pinfunction "INH_15") (pintype "input"))
      (node (ref "IC6") (pin "5") (pinfunction "G_5") (pintype "input"))
      (node (ref "IC6") (pin "6") (pinfunction "H_6") (pintype "input"))
      (node (ref "IC6") (pin "8") (pinfunction "GND_8") (pintype "power_in"))
      (node (ref "IC7") (pin "3") (pinfunction "+IN_3") (pintype "input"))
      (node (ref "IC7") (pin "4") (pinfunction "V-_4") (pintype "power_in"))
      (node (ref "IC8") (pin "GND") (pinfunction "GND_GND") (pintype "input"))
      (node (ref "IC9") (pin "GND") (pinfunction "GND_GND") (pintype "input"))
      (node (ref "J1") (pin "GND") (pinfunction "1_GND") (pintype "passive"))
      (node (ref "J1") (pin "GND2") (pinfunction "4_GND2") (pintype "passive"))
      (node (ref "J2") (pin "GND") (pinfunction "1_GND") (pintype "passive"))
      (node (ref "J2") (pin "GND2") (pinfunction "4_GND2") (pintype "passive"))
      (node (ref "J3") (pin "GND") (pinfunction "1_GND") (pintype "passive"))
      (node (ref "J3") (pin "GND2") (pinfunction "4_GND2") (pintype "passive"))
      (node (ref "J4") (pin "GND") (pinfunction "1_GND") (pintype "passive"))
      (node (ref "J4") (pin "GND2") (pinfunction "4_GND2") (pintype "passive"))
      (node (ref "J5") (pin "GND") (pinfunction "1_GND") (pintype "passive"))
      (node (ref "J5") (pin "GND2") (pinfunction "4_GND2") (pintype "passive"))
      (node (ref "J6") (pin "GND") (pinfunction "1_GND") (pintype "passive"))
      (node (ref "J6") (pin "GND2") (pinfunction "4_GND2") (pintype "passive"))
      (node (ref "J6") (pin "SW") (pinfunction "3_SW") (pintype "passive"))
      (node (ref "J7") (pin "10") (pinfunction "10_10") (pintype "passive"))
      (node (ref "J7") (pin "11") (pinfunction "11_11") (pintype "passive"))
      (node (ref "J7") (pin "12") (pinfunction "12_12") (pintype "passive"))
      (node (ref "J7") (pin "13") (pinfunction "13_13") (pintype "passive"))
      (node (ref "J7") (pin "14") (pinfunction "14_14") (pintype "passive"))
      (node (ref "J7") (pin "9") (pinfunction "9_9") (pintype "passive"))
      (node (ref "J8") (pin "S") (pinfunction "S_S") (pintype "passive"))
      (node (ref "J8") (pin "SN") (pinfunction "SN_SN") (pintype "passive"))
      (node (ref "J9") (pin "1") (pinfunction "1_1") (pintype "passive"))
      (node (ref "LED1") (pin "K") (pinfunction "C_K") (pintype "passive"))
      (node (ref "LED2") (pin "K") (pinfunction "C_K") (pintype "passive"))
      (node (ref "LED3") (pin "K") (pinfunction "C_K") (pintype "passive"))
      (node (ref "LED4") (pin "K") (pinfunction "C_K") (pintype "passive"))
      (node (ref "LED5") (pin "K") (pinfunction "C_K") (pintype "passive"))
      (node (ref "LED6") (pin "K") (pinfunction "C_K") (pintype "passive"))
      (node (ref "OK1") (pin "5") (pinfunction "GND_5") (pintype "passive"))
      (node (ref "Q1") (pin "3") (pinfunction "E_3") (pintype "passive"))
      (node (ref "R31") (pin "1") (pinfunction "1_1") (pintype "passive"))
      (node (ref "R8") (pin "3") (pinfunction "A_3") (pintype "passive"))
      (node (ref "S1") (pin "1") (pinfunction "S_1") (pintype "passive"))
      (node (ref "S1") (pin "2") (pinfunction "S1_2") (pintype "passive"))
      (node (ref "S2") (pin "1") (pinfunction "S_1") (pintype "passive"))
      (node (ref "S2") (pin "2") (pinfunction "S1_2") (pintype "passive"))
      (node (ref "S3") (pin "1") (pinfunction "S_1") (pintype "passive"))
      (node (ref "S3") (pin "2") (pinfunction "S1_2") (pintype "passive"))
      (node (ref "S4") (pin "1") (pinfunction "S_1") (pintype "passive"))
      (node (ref "S4") (pin "2") (pinfunction "S1_2") (pintype "passive"))
      (node (ref "S5") (pin "1") (pinfunction "S_1") (pintype "passive"))
      (node (ref "S5") (pin "2") (pinfunction "S1_2") (pintype "passive"))
      (node (ref "S6") (pin "1") (pinfunction "S_1") (pintype "passive"))
      (node (ref "S6") (pin "2") (pinfunction "S1_2") (pintype "passive"))
      (node (ref "SW1") (pin "C") (pinfunction "C_C") (pintype "passive"))
      (node (ref "SW1") (pin "D") (pinfunction "1_D") (pintype "passive"))
      (node (ref "U$3") (pin "1") (pinfunction "VSS_1") (pintype "power_in"))
      (node (ref "U$3") (pin "16") (pinfunction "K_16") (pintype "power_in"))
      (node (ref "U$3") (pin "5") (pinfunction "R/W_5") (pintype "input"))
      (node (ref "U1") (pin "6") (pinfunction "6_6") (pintype "passive"))
    )
    (net (code "14") (name "IO_ENABLE") (class "Default")
      (node (ref "IC4") (pin "26") (pinfunction "(TDO)PC4_26") (pintype "bidirectional"))
      (node (ref "IC5") (pin "12") (pinfunction "RCK_12") (pintype "input"))
      (node (ref "IC6") (pin "1") (pinfunction "SH/~{LD}_1") (pintype "input"))
    )
    (net (code "15") (name "IO_INPUT") (class "Default")
      (node (ref "IC4") (pin "28") (pinfunction "(TOSC1)PC6_28") (pintype "bidirectional"))
      (node (ref "IC6") (pin "9") (pinfunction "QH_9") (pintype "output"))
    )
    (net (code "16") (name "IO_OUTPUT") (class "Default")
      (node (ref "IC4") (pin "27") (pinfunction "(TDI)PC5_27") (pintype "bidirectional"))
      (node (ref "IC5") (pin "14") (pinfunction "SER_14") (pintype "input"))
    )
    (net (code "17") (name "IO_SCK") (class "Default")
      (node (ref "IC4") (pin "29") (pinfunction "(TOSC2)PC7_29") (pintype "bidirectional"))
      (node (ref "IC5") (pin "11") (pinfunction "SCK_11") (pintype "input"))
      (node (ref "IC6") (pin "2") (pinfunction "CLK_2") (pintype "input"))
    )
    (net (code "18") (name "LCD_DATA4") (class "Default")
      (node (ref "IC4") (pin "36") (pinfunction "(ADC4)PA4_36") (pintype "bidirectional"))
      (node (ref "U$3") (pin "11") (pinfunction "DB4_11") (pintype "bidirectional"))
    )
    (net (code "19") (name "LCD_DATA5") (class "Default")
      (node (ref "IC4") (pin "35") (pinfunction "(ADC5)PA5_35") (pintype "bidirectional"))
      (node (ref "U$3") (pin "12") (pinfunction "DB5_12") (pintype "bidirectional"))
    )
    (net (code "20") (name "LCD_DATA6") (class "Default")
      (node (ref "IC4") (pin "34") (pinfunction "(ADC6)PA6_34") (pintype "bidirectional"))
      (node (ref "U$3") (pin "13") (pinfunction "DB6_13") (pintype "bidirectional"))
    )
    (net (code "21") (name "LCD_DATA7") (class "Default")
      (node (ref "IC4") (pin "33") (pinfunction "(ADC7)PA7_33") (pintype "bidirectional"))
      (node (ref "U$3") (pin "14") (pinfunction "DB7_14") (pintype "bidirectional"))
    )
    (net (code "22") (name "LCD_ENABLE") (class "Default")
      (node (ref "IC4") (pin "38") (pinfunction "(ADC2)PA2_38") (pintype "bidirectional"))
      (node (ref "U$3") (pin "6") (pinfunction "E_6") (pintype "input"))
    )
    (net (code "23") (name "LCD_RS") (class "Default")
      (node (ref "IC4") (pin "37") (pinfunction "(ADC3)PA3_37") (pintype "bidirectional"))
      (node (ref "U$3") (pin "4") (pinfunction "RS_4") (pintype "input"))
    )
    (net (code "24") (name "MIDI_IN") (class "Default")
      (node (ref "IC4") (pin "14") (pinfunction "(RXD)PD0_14") (pintype "bidirectional"))
      (node (ref "OK1") (pin "6") (pinfunction "VO_6") (pintype "passive"))
      (node (ref "R5") (pin "1") (pinfunction "1_1") (pintype "passive"))
    )
    (net (code "25") (name "MISO") (class "Default")
      (node (ref "IC4") (pin "7") (pinfunction "(MISO)PB6_7") (pintype "bidirectional"))
      (node (ref "U1") (pin "1") (pinfunction "1_1") (pintype "passive"))
    )
    (net (code "26") (name "MOSI") (class "Default")
      (node (ref "IC3") (pin "4") (pinfunction "SDI_4") (pintype "input"))
      (node (ref "IC4") (pin "6") (pinfunction "(MOSI)PB5_6") (pintype "bidirectional"))
      (node (ref "U1") (pin "4") (pinfunction "4_4") (pintype "passive"))
    )
    (net (code "27") (name "Net-(C1-Pad2)") (class "Default")
      (node (ref "C1") (pin "2") (pinfunction "2_2") (pintype "passive"))
      (node (ref "J8") (pin "T") (pinfunction "T_T") (pintype "passive"))
      (node (ref "R1") (pin "2") (pinfunction "2_2") (pintype "passive"))
      (node (ref "R4") (pin "2") (pinfunction "2_2") (pintype "passive"))
    )
    (net (code "28") (name "Net-(C6-Pad-)") (class "Default")
      (node (ref "C6") (pin "-") (pinfunction "-_-") (pintype "passive"))
      (node (ref "R11") (pin "1") (pinfunction "1_1") (pintype "passive"))
    )
    (net (code "29") (name "Net-(C10-Pad2)") (class "Default")
      (node (ref "C10") (pin "2") (pinfunction "2_2") (pintype "passive"))
      (node (ref "C31") (pin "-") (pinfunction "-_-") (pintype "passive"))
      (node (ref "D3") (pin "A") (pinfunction "A_A") (pintype "passive"))
      (node (ref "D5") (pin "A") (pinfunction "A_A") (pintype "passive"))
      (node (ref "IC8") (pin "IN") (pinfunction "IN_IN") (pintype "input"))
    )
    (net (code "30") (name "Net-(C12-Pad1)") (class "Default")
      (node (ref "C12") (pin "1") (pinfunction "1_1") (pintype "passive"))
      (node (ref "C19") (pin "1") (pinfunction "1_1") (pintype "passive"))
      (node (ref "C29") (pin "+") (pinfunction "+_+") (pintype "passive"))
      (node (ref "D2") (pin "C") (pinfunction "C_C") (pintype "passive"))
      (node (ref "D7") (pin "C") (pinfunction "C_C") (pintype "passive"))
      (node (ref "D9") (pin "C") (pinfunction "C_C") (pintype "passive"))
      (node (ref "IC10") (pin "IN") (pinfunction "IN_IN") (pintype "input"))
      (node (ref "IC9") (pin "IN") (pinfunction "IN_IN") (pintype "input"))
    )
    (net (code "31") (name "Net-(C24-Pad-)") (class "Default")
      (node (ref "C24") (pin "-") (pinfunction "-_-") (pintype "passive"))
      (node (ref "R29") (pin "1") (pinfunction "1_1") (pintype "passive"))
    )
    (net (code "32") (name "Net-(C30-Pad1)") (class "Default")
      (node (ref "C30") (pin "1") (pinfunction "1_1") (pintype "passive"))
      (node (ref "D2") (pin "A") (pinfunction "A_A") (pintype "passive"))
      (node (ref "D3") (pin "C") (pinfunction "C_C") (pintype "passive"))
      (node (ref "J9") (pin "3") (pinfunction "3_3") (pintype "passive"))
    )
    (net (code "33") (name "Net-(IC2A--IN)") (class "Default")
      (node (ref "C1") (pin "1") (pinfunction "1_1") (pintype "passive"))
      (node (ref "IC2") (pin "2") (pinfunction "-IN_2") (pintype "input"))
      (node (ref "R4") (pin "1") (pinfunction "1_1") (pintype "passive"))
      (node (ref "R7") (pin "2") (pinfunction "2_2") (pintype "passive"))
    )
    (net (code "34") (name "Net-(IC2A-OUT)") (class "Default")
      (node (ref "IC2") (pin "1") (pinfunction "OUT_1") (pintype "output"))
      (node (ref "R1") (pin "1") (pinfunction "1_1") (pintype "passive"))
    )
    (net (code "35") (name "Net-(IC2B--IN)") (class "Default")
      (node (ref "C7") (pin "1") (pinfunction "1_1") (pintype "passive"))
      (node (ref "IC2") (pin "6") (pinfunction "-IN_6") (pintype "input"))
      (node (ref "R11") (pin "2") (pinfunction "2_2") (pintype "passive"))
      (node (ref "R15") (pin "1") (pinfunction "1_1") (pintype "passive"))
    )
    (net (code "36") (name "Net-(IC2B-OUT)") (class "Default")
      (node (ref "C7") (pin "2") (pinfunction "2_2") (pintype "passive"))
      (node (ref "IC2") (pin "7") (pinfunction "OUT_7") (pintype "output"))
      (node (ref "J4") (pin "TIP") (pinfunction "2_TIP") (pintype "passive"))
      (node (ref "R15") (pin "2") (pinfunction "2_2") (pintype "passive"))
    )
    (net (code "37") (name "Net-(IC2C--IN)") (class "Default")
      (node (ref "C8") (pin "1") (pinfunction "1_1") (pintype "passive"))
      (node (ref "IC2") (pin "9") (pinfunction "-IN_9") (pintype "input"))
      (node (ref "R10") (pin "2") (pinfunction "2_2") (pintype "passive"))
      (node (ref "R12") (pin "2") (pinfunction "2_2") (pintype "passive"))
      (node (ref "R16") (pin "1") (pinfunction "1_1") (pintype "passive"))
    )
    (net (code "38") (name "Net-(IC2C-OUT)") (class "Default")
      (node (ref "C8") (pin "2") (pinfunction "2_2") (pintype "passive"))
      (node (ref "IC2") (pin "8") (pinfunction "OUT_8") (pintype "output"))
      (node (ref "J3") (pin "TIP") (pinfunction "2_TIP") (pintype "passive"))
      (node (ref "R16") (pin "2") (pinfunction "2_2") (pintype "passive"))
    )
    (net (code "39") (name "Net-(IC2D--IN)") (class "Default")
      (node (ref "IC2") (pin "13") (pinfunction "-IN_13") (pintype "input"))
      (node (ref "IC2") (pin "14") (pinfunction "OUT_14") (pintype "output"))
    )
    (net (code "40") (name "Net-(IC4-AREF)") (class "Default")
      (node (ref "C18") (pin "1") (pinfunction "1_1") (pintype "passive"))
      (node (ref "IC4") (pin "32") (pinfunction "AREF_32") (pintype "passive"))
    )
    (net (code "41") (name "Net-(IC4-XTAL1)") (class "Default")
      (node (ref "C13") (pin "2") (pinfunction "2_2") (pintype "passive"))
      (node (ref "IC4") (pin "13") (pinfunction "XTAL1_13") (pintype "bidirectional"))
      (node (ref "Q2") (pin "1") (pinfunction "1_1") (pintype "passive"))
    )
    (net (code "42") (name "Net-(IC4-XTAL2)") (class "Default")
      (node (ref "C14") (pin "2") (pinfunction "2_2") (pintype "passive"))
      (node (ref "IC4") (pin "12") (pinfunction "XTAL2_12") (pintype "bidirectional"))
      (node (ref "Q2") (pin "2") (pinfunction "2_2") (pintype "passive"))
    )
    (net (code "43") (name "Net-(IC5A-QA)") (class "Default")
      (node (ref "IC5") (pin "15") (pinfunction "QA_15") (pintype "tri_state"))
      (node (ref "R19") (pin "1") (pinfunction "1_1") (pintype "passive"))
    )
    (net (code "44") (name "Net-(IC5A-QB)") (class "Default")
      (node (ref "IC5") (pin "1") (pinfunction "QB_1") (pintype "tri_state"))
      (node (ref "R20") (pin "1") (pinfunction "1_1") (pintype "passive"))
    )
    (net (code "45") (name "Net-(IC5A-QC)") (class "Default")
      (node (ref "IC5") (pin "2") (pinfunction "QC_2") (pintype "tri_state"))
      (node (ref "R21") (pin "1") (pinfunction "1_1") (pintype "passive"))
    )
    (net (code "46") (name "Net-(IC5A-QD)") (class "Default")
      (node (ref "IC5") (pin "3") (pinfunction "QD_3") (pintype "tri_state"))
      (node (ref "R22") (pin "1") (pinfunction "1_1") (pintype "passive"))
    )
    (net (code "47") (name "Net-(IC5A-QE)") (class "Default")
      (node (ref "IC5") (pin "4") (pinfunction "QE_4") (pintype "tri_state"))
      (node (ref "R23") (pin "1") (pinfunction "1_1") (pintype "passive"))
    )
    (net (code "48") (name "Net-(IC5A-QF)") (class "Default")
      (node (ref "IC5") (pin "5") (pinfunction "QF_5") (pintype "tri_state"))
      (node (ref "R24") (pin "1") (pinfunction "1_1") (pintype "passive"))
    )
    (net (code "49") (name "Net-(IC6A-A)") (class "Default")
      (node (ref "IC6") (pin "11") (pinfunction "A_11") (pintype "input"))
      (node (ref "RN1") (pin "7") (pinfunction "7_7") (pintype "passive"))
      (node (ref "S1") (pin "3") (pinfunction "P_3") (pintype "passive"))
      (node (ref "S1") (pin "4") (pinfunction "P1_4") (pintype "passive"))
    )
    (net (code "50") (name "Net-(IC6A-B)") (class "Default")
      (node (ref "IC6") (pin "12") (pinfunction "B_12") (pintype "input"))
      (node (ref "RN1") (pin "6") (pinfunction "6_6") (pintype "passive"))
      (node (ref "S2") (pin "3") (pinfunction "P_3") (pintype "passive"))
      (node (ref "S2") (pin "4") (pinfunction "P1_4") (pintype "passive"))
    )
    (net (code "51") (name "Net-(IC6A-C)") (class "Default")
      (node (ref "IC6") (pin "13") (pinfunction "C_13") (pintype "input"))
      (node (ref "RN1") (pin "5") (pinfunction "5_5") (pintype "passive"))
      (node (ref "S3") (pin "3") (pinfunction "P_3") (pintype "passive"))
      (node (ref "S3") (pin "4") (pinfunction "P1_4") (pintype "passive"))
    )
    (net (code "52") (name "Net-(IC6A-D)") (class "Default")
      (node (ref "IC6") (pin "14") (pinfunction "D_14") (pintype "input"))
      (node (ref "RN1") (pin "4") (pinfunction "4_4") (pintype "passive"))
      (node (ref "S4") (pin "3") (pinfunction "P_3") (pintype "passive"))
      (node (ref "S4") (pin "4") (pinfunction "P1_4") (pintype "passive"))
    )
    (net (code "53") (name "Net-(IC6A-E)") (class "Default")
      (node (ref "IC6") (pin "3") (pinfunction "E_3") (pintype "input"))
      (node (ref "RN1") (pin "3") (pinfunction "3_3") (pintype "passive"))
      (node (ref "S5") (pin "3") (pinfunction "P_3") (pintype "passive"))
      (node (ref "S5") (pin "4") (pinfunction "P1_4") (pintype "passive"))
    )
    (net (code "54") (name "Net-(IC6A-F)") (class "Default")
      (node (ref "IC6") (pin "4") (pinfunction "F_4") (pintype "input"))
      (node (ref "RN1") (pin "2") (pinfunction "2_2") (pintype "passive"))
      (node (ref "S6") (pin "3") (pinfunction "P_3") (pintype "passive"))
      (node (ref "S6") (pin "4") (pinfunction "P1_4") (pintype "passive"))
    )
    (net (code "55") (name "Net-(IC7A--IN)") (class "Default")
      (node (ref "IC7") (pin "2") (pinfunction "-IN_2") (pintype "input"))
      (node (ref "R30") (pin "1") (pinfunction "1_1") (pintype "passive"))
      (node (ref "R32") (pin "2") (pinfunction "2_2") (pintype "passive"))
    )
    (net (code "56") (name "Net-(IC7B-+IN)") (class "Default")
      (node (ref "C25") (pin "1") (pinfunction "1_1") (pintype "passive"))
      (node (ref "IC7") (pin "5") (pinfunction "+IN_5") (pintype "input"))
      (node (ref "R31") (pin "2") (pinfunction "2_2") (pintype "passive"))
      (node (ref "R33") (pin "1") (pinfunction "1_1") (pintype "passive"))
    )
    (net (code "57") (name "Net-(IC7B--IN)") (class "Default")
      (node (ref "C22") (pin "1") (pinfunction "1_1") (pintype "passive"))
      (node (ref "IC7") (pin "6") (pinfunction "-IN_6") (pintype "input"))
      (node (ref "R28") (pin "1") (pinfunction "1_1") (pintype "passive"))
      (node (ref "R29") (pin "2") (pinfunction "2_2") (pintype "passive"))
    )
    (net (code "58") (name "Net-(J1-2)") (class "Default")
      (node (ref "J1") (pin "TIP") (pinfunction "2_TIP") (pintype "passive"))
      (node (ref "R25") (pin "2") (pinfunction "2_2") (pintype "passive"))
    )
    (net (code "59") (name "Net-(J2-2)") (class "Default")
      (node (ref "J2") (pin "TIP") (pinfunction "2_TIP") (pintype "passive"))
      (node (ref "R27") (pin "2") (pinfunction "2_2") (pintype "passive"))
    )
    (net (code "60") (name "Net-(J5-2)") (class "Default")
      (node (ref "C24") (pin "+") (pinfunction "+_+") (pintype "passive"))
      (node (ref "J5") (pin "TIP") (pinfunction "2_TIP") (pintype "passive"))
      (node (ref "R32") (pin "1") (pinfunction "1_1") (pintype "passive"))
      (node (ref "R7") (pin "1") (pinfunction "1_1") (pintype "passive"))
    )
    (net (code "61") (name "Net-(J6-2)") (class "Default")
      (node (ref "J6") (pin "TIP") (pinfunction "2_TIP") (pintype "passive"))
      (node (ref "R18") (pin "1") (pinfunction "1_1") (pintype "passive"))
    )
    (net (code "62") (name "Net-(LED1-PadA)") (class "Default")
      (node (ref "LED1") (pin "A") (pinfunction "A_A") (pintype "passive"))
      (node (ref "R19") (pin "2") (pinfunction "2_2") (pintype "passive"))
    )
    (net (code "63") (name "Net-(LED2-PadA)") (class "Default")
      (node (ref "LED2") (pin "A") (pinfunction "A_A") (pintype "passive"))
      (node (ref "R20") (pin "2") (pinfunction "2_2") (pintype "passive"))
    )
    (net (code "64") (name "Net-(LED3-PadA)") (class "Default")
      (node (ref "LED3") (pin "A") (pinfunction "A_A") (pintype "passive"))
      (node (ref "R21") (pin "2") (pinfunction "2_2") (pintype "passive"))
    )
    (net (code "65") (name "Net-(LED4-PadA)") (class "Default")
      (node (ref "LED4") (pin "A") (pinfunction "A_A") (pintype "passive"))
      (node (ref "R22") (pin "2") (pinfunction "2_2") (pintype "passive"))
    )
    (net (code "66") (name "Net-(LED5-PadA)") (class "Default")
      (node (ref "LED5") (pin "A") (pinfunction "A_A") (pintype "passive"))
      (node (ref "R23") (pin "2") (pinfunction "2_2") (pintype "passive"))
    )
    (net (code "67") (name "Net-(LED6-PadA)") (class "Default")
      (node (ref "LED6") (pin "A") (pinfunction "A_A") (pintype "passive"))
      (node (ref "R24") (pin "2") (pinfunction "2_2") (pintype "passive"))
    )
    (net (code "68") (name "Net-(OK1-A)") (class "Default")
      (node (ref "D1") (pin "C") (pinfunction "C_C") (pintype "passive"))
      (node (ref "OK1") (pin "2") (pinfunction "A_2") (pintype "passive"))
      (node (ref "R3") (pin "2") (pinfunction "2_2") (pintype "passive"))
    )
    (net (code "69") (name "Net-(OK1-C)") (class "Default")
      (node (ref "D1") (pin "A") (pinfunction "A_A") (pintype "passive"))
      (node (ref "OK1") (pin "3") (pinfunction "C_3") (pintype "passive"))
      (node (ref "X1") (pin "5") (pinfunction "5_5") (pintype "passive"))
    )
    (net (code "70") (name "Net-(Q1-B)") (class "Default")
      (node (ref "Q1") (pin "2") (pinfunction "B_2") (pintype "passive"))
      (node (ref "R18") (pin "2") (pinfunction "2_2") (pintype "passive"))
    )
    (net (code "71") (name "Net-(R3-Pad1)") (class "Default")
      (node (ref "R3") (pin "1") (pinfunction "1_1") (pintype "passive"))
      (node (ref "X1") (pin "4") (pinfunction "4_4") (pintype "passive"))
    )
    (net (code "72") (name "Net-(R8-S)") (class "Default")
      (node (ref "R8") (pin "2") (pinfunction "S_2") (pintype "passive"))
      (node (ref "U$3") (pin "3") (pinfunction "VO_3") (pintype "bidirectional"))
    )
    (net (code "73") (name "Net-(R9-E)") (class "Default")
      (node (ref "R6") (pin "1") (pinfunction "1_1") (pintype "passive"))
      (node (ref "R9") (pin "1") (pinfunction "E_1") (pintype "passive"))
    )
    (net (code "74") (name "Net-(R10-Pad1)") (class "Default")
      (node (ref "R10") (pin "1") (pinfunction "1_1") (pintype "passive"))
      (node (ref "R6") (pin "2") (pinfunction "2_2") (pintype "passive"))
    )
    (net (code "75") (name "Net-(R13-E)") (class "Default")
      (node (ref "R12") (pin "1") (pinfunction "1_1") (pintype "passive"))
      (node (ref "R13") (pin "1") (pinfunction "E_1") (pintype "passive"))
    )
    (net (code "76") (name "Net-(U$3-A)") (class "Default")
      (node (ref "R14") (pin "2") (pinfunction "2_2") (pintype "passive"))
      (node (ref "U$3") (pin "15") (pinfunction "A_15") (pintype "power_in"))
    )
    (net (code "77") (name "PITCH_DETECTOR") (class "Default")
      (node (ref "IC4") (pin "20") (pinfunction "(ICP)PD6_20") (pintype "bidirectional"))
      (node (ref "IC7") (pin "1") (pinfunction "OUT_1") (pintype "output"))
      (node (ref "R30") (pin "2") (pinfunction "2_2") (pintype "passive"))
    )
    (net (code "78") (name "REF_-4.096") (class "Default")
      (node (ref "C3") (pin "1") (pinfunction "1_1") (pintype "passive"))
      (node (ref "IC1") (pin "3") (pinfunction "A_3") (pintype "passive"))
      (node (ref "R2") (pin "2") (pinfunction "2_2") (pintype "passive"))
      (node (ref "R9") (pin "2") (pinfunction "S_2") (pintype "passive"))
      (node (ref "R9") (pin "3") (pinfunction "A_3") (pintype "passive"))
    )
    (net (code "79") (name "RESET") (class "Default")
      (node (ref "C20") (pin "1") (pinfunction "1_1") (pintype "passive"))
      (node (ref "IC4") (pin "9") (pinfunction "RESET_9") (pintype "input"))
      (node (ref "R26") (pin "1") (pinfunction "1_1") (pintype "passive"))
      (node (ref "U1") (pin "5") (pinfunction "5_5") (pintype "passive"))
    )
    (net (code "80") (name "SCK") (class "Default")
      (node (ref "IC3") (pin "3") (pinfunction "SCK_3") (pintype "input"))
      (node (ref "IC4") (pin "8") (pinfunction "(SCK)PB7_8") (pintype "bidirectional"))
      (node (ref "U1") (pin "3") (pinfunction "3_3") (pintype "passive"))
    )
    (net (code "81") (name "SS") (class "Default")
      (node (ref "IC3") (pin "2") (pinfunction "#CS_2") (pintype "input"))
      (node (ref "IC4") (pin "5") (pinfunction "(SS)PB4_5") (pintype "bidirectional"))
    )
    (net (code "82") (name "VCC") (class "Default")
      (node (ref "C27") (pin "+") (pinfunction "+_+") (pintype "passive"))
      (node (ref "C4") (pin "1") (pinfunction "1_1") (pintype "passive"))
      (node (ref "D6") (pin "C") (pinfunction "C_C") (pintype "passive"))
      (node (ref "D7") (pin "A") (pinfunction "A_A") (pintype "passive"))
      (node (ref "IC2") (pin "4") (pinfunction "V+_4") (pintype "power_in"))
      (node (ref "IC9") (pin "OUT") (pinfunction "OUT_OUT") (pintype "passive"))
      (node (ref "J7") (pin "7") (pinfunction "7_7") (pintype "passive"))
      (node (ref "J7") (pin "8") (pinfunction "8_8") (pintype "passive"))
    )
    (net (code "83") (name "VEE") (class "Default")
      (node (ref "C28") (pin "-") (pinfunction "-_-") (pintype "passive"))
      (node (ref "C5") (pin "2") (pinfunction "2_2") (pintype "passive"))
      (node (ref "D4") (pin "A") (pinfunction "A_A") (pintype "passive"))
      (node (ref "D5") (pin "C") (pinfunction "C_C") (pintype "passive"))
      (node (ref "IC2") (pin "11") (pinfunction "V-_11") (pintype "power_in"))
      (node (ref "IC8") (pin "OUT") (pinfunction "OUT_OUT") (pintype "passive"))
      (node (ref "J7") (pin "15") (pinfunction "15_15") (pintype "passive"))
      (node (ref "J7") (pin "16") (pinfunction "16_16") (pintype "passive"))
      (node (ref "R2") (pin "1") (pinfunction "1_1") (pintype "passive"))
    )
    (net (code "84") (name "unconnected-(IC4-(ADC1)PA1-Pad39)") (class "Default")
      (node (ref "IC4") (pin "39") (pinfunction "(ADC1)PA1_39") (pintype "bidirectional"))
    )
    (net (code "85") (name "unconnected-(IC4-(AIN0{slash}INT2)PB2-Pad3)") (class "Default")
      (node (ref "IC4") (pin "3") (pinfunction "(AIN0/INT2)PB2_3") (pintype "bidirectional"))
    )
    (net (code "86") (name "unconnected-(IC4-(AIN1{slash}OC0)PB3-Pad4)") (class "Default")
      (node (ref "IC4") (pin "4") (pinfunction "(AIN1/OC0)PB3_4") (pintype "bidirectional"))
    )
    (net (code "87") (name "unconnected-(IC4-(OC1A)PD5-Pad19)") (class "Default")
      (node (ref "IC4") (pin "19") (pinfunction "(OC1A)PD5_19") (pintype "bidirectional"))
    )
    (net (code "88") (name "unconnected-(IC4-(OC2)PD7-Pad21)") (class "Default")
      (node (ref "IC4") (pin "21") (pinfunction "(OC2)PD7_21") (pintype "bidirectional"))
    )
    (net (code "89") (name "unconnected-(IC4-(T0{slash}XCK)PB0-Pad1)") (class "Default")
      (node (ref "IC4") (pin "1") (pinfunction "(T0/XCK)PB0_1") (pintype "bidirectional"))
    )
    (net (code "90") (name "unconnected-(IC4-(T1)PB1-Pad2)") (class "Default")
      (node (ref "IC4") (pin "2") (pinfunction "(T1)PB1_2") (pintype "bidirectional"))
    )
    (net (code "91") (name "unconnected-(IC4-(TMS)PC3-Pad25)") (class "Default")
      (node (ref "IC4") (pin "25") (pinfunction "(TMS)PC3_25") (pintype "bidirectional"))
    )
    (net (code "92") (name "unconnected-(IC4-(TXD)PD1-Pad15)") (class "Default")
      (node (ref "IC4") (pin "15") (pinfunction "(TXD)PD1_15") (pintype "bidirectional"))
    )
    (net (code "93") (name "unconnected-(IC5A-QG-Pad6)") (class "Default")
      (node (ref "IC5") (pin "6") (pinfunction "QG_6") (pintype "tri_state"))
    )
    (net (code "94") (name "unconnected-(IC5A-QH*-Pad9)") (class "Default")
      (node (ref "IC5") (pin "9") (pinfunction "QH*_9") (pintype "tri_state"))
    )
    (net (code "95") (name "unconnected-(IC5A-QH-Pad7)") (class "Default")
      (node (ref "IC5") (pin "7") (pinfunction "QH_7") (pintype "tri_state"))
    )
    (net (code "96") (name "unconnected-(IC6A-~{QH}-Pad7)") (class "Default")
      (node (ref "IC6") (pin "7") (pinfunction "~{QH}_7") (pintype "output"))
    )
    (net (code "97") (name "unconnected-(J1-3-PadSW)") (class "Default")
      (node (ref "J1") (pin "SW") (pinfunction "3_SW") (pintype "passive"))
    )
    (net (code "98") (name "unconnected-(J2-3-PadSW)") (class "Default")
      (node (ref "J2") (pin "SW") (pinfunction "3_SW") (pintype "passive"))
    )
    (net (code "99") (name "unconnected-(J3-3-PadSW)") (class "Default")
      (node (ref "J3") (pin "SW") (pinfunction "3_SW") (pintype "passive"))
    )
    (net (code "100") (name "unconnected-(J4-3-PadSW)") (class "Default")
      (node (ref "J4") (pin "SW") (pinfunction "3_SW") (pintype "passive"))
    )
    (net (code "101") (name "unconnected-(J5-3-PadSW)") (class "Default")
      (node (ref "J5") (pin "SW") (pinfunction "3_SW") (pintype "passive"))
    )
    (net (code "102") (name "unconnected-(J7-Pad1)") (class "Default")
      (node (ref "J7") (pin "1") (pinfunction "1_1") (pintype "passive"))
    )
    (net (code "103") (name "unconnected-(J7-Pad2)") (class "Default")
      (node (ref "J7") (pin "2") (pinfunction "2_2") (pintype "passive"))
    )
    (net (code "104") (name "unconnected-(J7-Pad3)") (class "Default")
      (node (ref "J7") (pin "3") (pinfunction "3_3") (pintype "passive"))
    )
    (net (code "105") (name "unconnected-(J7-Pad4)") (class "Default")
      (node (ref "J7") (pin "4") (pinfunction "4_4") (pintype "passive"))
    )
    (net (code "106") (name "unconnected-(J8-PadTN)") (class "Default")
      (node (ref "J8") (pin "TN") (pinfunction "TN_TN") (pintype "passive"))
    )
    (net (code "107") (name "unconnected-(J9-Pad2)") (class "Default")
      (node (ref "J9") (pin "2") (pinfunction "2_2") (pintype "passive"))
    )
    (net (code "108") (name "unconnected-(OK1-VB-Pad7)") (class "Default")
      (node (ref "OK1") (pin "7") (pinfunction "VB_7") (pintype "passive"))
    )
    (net (code "109") (name "unconnected-(U$3-DB0-Pad7)") (class "Default")
      (node (ref "U$3") (pin "7") (pinfunction "DB0_7") (pintype "bidirectional"))
    )
    (net (code "110") (name "unconnected-(U$3-DB1-Pad8)") (class "Default")
      (node (ref "U$3") (pin "8") (pinfunction "DB1_8") (pintype "bidirectional"))
    )
    (net (code "111") (name "unconnected-(U$3-DB2-Pad9)") (class "Default")
      (node (ref "U$3") (pin "9") (pinfunction "DB2_9") (pintype "bidirectional"))
    )
    (net (code "112") (name "unconnected-(U$3-DB3-Pad10)") (class "Default")
      (node (ref "U$3") (pin "10") (pinfunction "DB3_10") (pintype "bidirectional"))
    )
    (net (code "113") (name "unconnected-(X1-Pad1)") (class "Default")
      (node (ref "X1") (pin "1") (pinfunction "1_1") (pintype "passive"))
    )
    (net (code "114") (name "unconnected-(X1-Pad2)") (class "Default")
      (node (ref "X1") (pin "2") (pinfunction "2_2") (pintype "passive"))
    )
    (net (code "115") (name "unconnected-(X1-Pad3)") (class "Default")
      (node (ref "X1") (pin "3") (pinfunction "3_3") (pintype "passive"))
    )
  )
)
